# PowerDDFK.net
KiCad netlist of a schematic drawn in Altium Designer
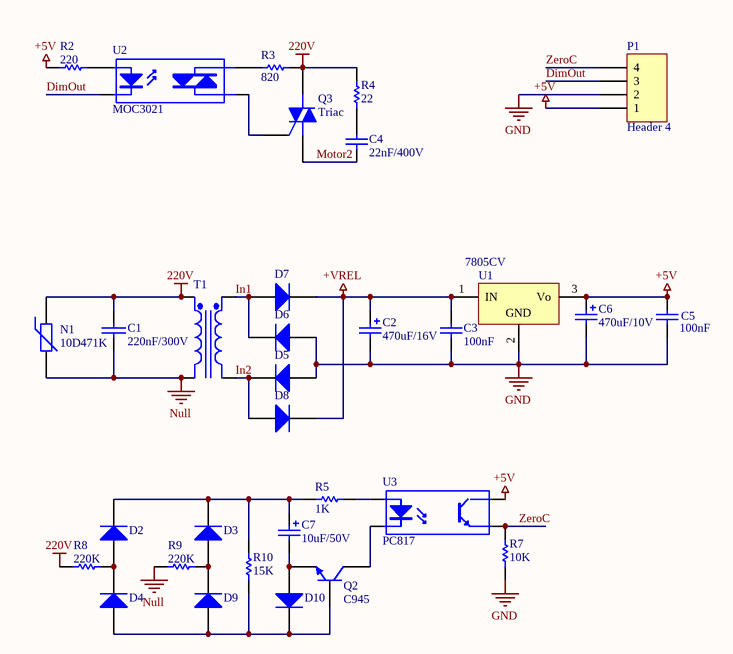
[diagram p0: PowerDDFK.SchDoc]

(export (version "E")
  (design (tool "Eeschema 10.0.6"))
  (components
    (comp (ref "C1")
      (value "220nF/300V")
      (footprint "Cap15-20")
      (description "Line Cap")
      (libsource (lib "*") (part "CAP"))
    )
    (comp (ref "C2")
      (value "470uF/16V")
      (footprint "RB.2/.4")
      (description "Polarized Capacitor")
      (fields (field (name "PUBLISHER") "Altium Limited"))
      (libsource (lib "MySchLib") (part "Cap Pol"))
    )
    (comp (ref "C3")
      (value "100nF")
      (footprint "RAD0.2")
      (description "Capacitor np")
      (fields (field (name "PUBLISHER") "Altium Limited"))
      (libsource (lib "MySchLib") (part "Cap"))
    )
    (comp (ref "C4")
      (value "22nF/400V")
      (footprint "Cap10")
      (description "Capacitor")
      (fields (field (name "PUBLISHER") "Altium Limited"))
      (libsource (lib "MySchLib") (part "Cap"))
    )
    (comp (ref "C5")
      (value "100nF")
      (footprint "RAD0.2")
      (description "Capacitor np")
      (fields (field (name "PUBLISHER") "Altium Limited"))
      (libsource (lib "MySchLib") (part "Cap"))
    )
    (comp (ref "C6")
      (value "470uF/10V")
      (footprint "RB.2/.4")
      (description "Polarized Capacitor")
      (fields (field (name "PUBLISHER") "Altium Limited"))
      (libsource (lib "MySchLib") (part "Cap Pol"))
    )
    (comp (ref "C7")
      (value "10uF/50V")
      (footprint "RB.1/.2")
      (description "Polarized Capacitor")
      (fields (field (name "PUBLISHER") "Altium Limited"))
      (libsource (lib "MySchLib") (part "Cap Pol"))
    )
    (comp (ref "D2")
      (value "1N4007")
      (footprint "DIODE0.4")
      (fields (field (name "PUBLISHER") "Altium Limited"))
      (libsource (lib "MySchLib") (part "Diode"))
    )
    (comp (ref "D3")
      (value "1N4007")
      (footprint "DIODE0.4")
      (fields (field (name "PUBLISHER") "Altium Limited"))
      (libsource (lib "MySchLib") (part "Diode"))
    )
    (comp (ref "D4")
      (value "1N4007")
      (footprint "DIODE0.4")
      (fields (field (name "PUBLISHER") "Altium Limited"))
      (libsource (lib "MySchLib") (part "Diode"))
    )
    (comp (ref "D5")
      (value "1N4007")
      (footprint "DIODE0.4")
      (fields (field (name "PUBLISHER") "Altium Limited"))
      (libsource (lib "MySchLib") (part "Diode"))
    )
    (comp (ref "D6")
      (value "1N4007")
      (footprint "DIODE0.4")
      (fields (field (name "PUBLISHER") "Altium Limited"))
      (libsource (lib "MySchLib") (part "Diode"))
    )
    (comp (ref "D7")
      (value "1N4007")
      (footprint "DIODE0.4")
      (fields (field (name "PUBLISHER") "Altium Limited"))
      (libsource (lib "MySchLib") (part "Diode"))
    )
    (comp (ref "D8")
      (value "1N4007")
      (footprint "DIODE0.4")
      (fields (field (name "PUBLISHER") "Altium Limited"))
      (libsource (lib "MySchLib") (part "Diode"))
    )
    (comp (ref "D9")
      (value "1N4007")
      (footprint "DIODE0.4")
      (fields (field (name "PUBLISHER") "Altium Limited"))
      (libsource (lib "MySchLib") (part "Diode"))
    )
    (comp (ref "D10")
      (value "1N4007")
      (footprint "DIODE0.4")
      (fields (field (name "PUBLISHER") "Altium Limited"))
      (libsource (lib "MySchLib") (part "Diode"))
    )
    (comp (ref "N1")
      (value "10D471K")
      (footprint "varistor-10mil")
      (fields (field (name "PUBLISHER") "Altium Limited"))
      (libsource (lib "Miscellaneous Devices") (part "Res Varistor"))
    )
    (comp (ref "P1")
      (value "Header 4")
      (footprint "CON4")
      (description "Header, 4-Pin")
      (fields (field (name "PUBLISHER") "Altium Limited"))
      (libsource (lib "Miscellaneous Connectors") (part "Header 4"))
    )
    (comp (ref "Q2")
      (value "C945")
      (footprint "TO92BS2")
      (description "NPN General Purpose Amplifier")
      (fields (field (name "PUBLISHER") "Altium Limited"))
      (libsource (lib "MySchLib") (part "BC337"))
    )
    (comp (ref "Q3")
      (value "Triac")
      (footprint "TO-220HS28")
      (description "Silicon Bidirectional Triode Thyristor")
      (fields (field (name "PUBLISHER") "Altium Limited"))
      (libsource (lib "Miscellaneous Devices") (part "Triac"))
    )
    (comp (ref "R2")
      (value "220")
      (footprint "RES0.35")
      (description "Resistor")
      (fields (field (name "PUBLISHER") "Altium Limited"))
      (libsource (lib "MySchLib") (part "Resistor"))
    )
    (comp (ref "R3")
      (value "820")
      (footprint "RES0.35")
      (description "Resistor")
      (fields (field (name "PUBLISHER") "Altium Limited"))
      (libsource (lib "MySchLib") (part "Resistor"))
    )
    (comp (ref "R4")
      (value "22")
      (footprint "RES0.35")
      (description "Resistor")
      (fields (field (name "PUBLISHER") "Altium Limited"))
      (libsource (lib "MySchLib") (part "Resistor"))
    )
    (comp (ref "R5")
      (value "1K")
      (footprint "RES0.35")
      (description "Resistor")
      (fields (field (name "PUBLISHER") "Altium Limited"))
      (libsource (lib "MySchLib") (part "Resistor"))
    )
    (comp (ref "R7")
      (value "10K")
      (footprint "RES0.35")
      (description "Resistor")
      (fields (field (name "PUBLISHER") "Altium Limited"))
      (libsource (lib "MySchLib") (part "Resistor"))
    )
    (comp (ref "R8")
      (value "220K")
      (footprint "RES0.35")
      (description "Resistor")
      (fields (field (name "PUBLISHER") "Altium Limited"))
      (libsource (lib "MySchLib") (part "Resistor"))
    )
    (comp (ref "R9")
      (value "220K")
      (footprint "RES0.35")
      (description "Resistor")
      (fields (field (name "PUBLISHER") "Altium Limited"))
      (libsource (lib "MySchLib") (part "Resistor"))
    )
    (comp (ref "R10")
      (value "15K")
      (footprint "RES0.35")
      (description "Resistor")
      (fields (field (name "PUBLISHER") "Altium Limited"))
      (libsource (lib "MySchLib") (part "Resistor"))
    )
    (comp (ref "T1")
      (value "Transformer")
      (footprint "Trans200mA")
      (description "6Volt-300mA")
      (fields (field (name "PUBLISHER") "Altium Limited"))
      (libsource (lib "MySchLib") (part "Transformer"))
    )
    (comp (ref "U1")
      (value "7805CV")
      (footprint "TO-220HS28")
      (description "Positive Voltage Regulator")
      (fields (field (name "PUBLISHER") "Altium Limited"))
      (libsource (lib "MySchLib") (part "7805"))
    )
    (comp (ref "U2")
      (value "MOC3021")
      (footprint "DIP6")
      (description "Opto-Triac")
      (fields (field (name "PUBLISHER") "Altium Limited"))
      (libsource (lib "MySchLib") (part "Opto TRIAC_1"))
    )
    (comp (ref "U3")
      (value "PC817")
      (footprint "DIP4-OPTO")
      (description "4-Pin Phototransistor Optocoupler")
      (fields (field (name "PUBLISHER") "Altium Limited"))
      (libsource (lib "MySchLib") (part "Optoisolator1"))
    )
  )
  (nets
    (net (code "1") (name "+5V") (class "Default")
      (node (ref "C5") (pin "2") (pinfunction "2_2") (pintype "passive"))
      (node (ref "C6") (pin "1") (pinfunction "1_1") (pintype "passive"))
      (node (ref "P1") (pin "1") (pinfunction "1_1") (pintype "passive"))
      (node (ref "R2") (pin "1") (pinfunction "1_1") (pintype "passive"))
      (node (ref "U1") (pin "3") (pinfunction "Vo_3") (pintype "power_in"))
      (node (ref "U3") (pin "4") (pinfunction "C_4") (pintype "passive"))
    )
    (net (code "2") (name "+VREL") (class "Default")
      (node (ref "C2") (pin "1") (pinfunction "1_1") (pintype "passive"))
      (node (ref "C3") (pin "2") (pinfunction "2_2") (pintype "passive"))
      (node (ref "D7") (pin "2") (pinfunction "K_2") (pintype "passive"))
      (node (ref "D8") (pin "2") (pinfunction "K_2") (pintype "passive"))
      (node (ref "U1") (pin "1") (pinfunction "IN_1") (pintype "power_in"))
    )
    (net (code "3") (name "/DimOut") (class "Default")
      (node (ref "P1") (pin "3") (pinfunction "3_3") (pintype "passive"))
      (node (ref "U2") (pin "2") (pinfunction "K_2") (pintype "passive"))
    )
    (net (code "4") (name "/In1") (class "Default")
      (node (ref "D6") (pin "2") (pinfunction "K_2") (pintype "passive"))
      (node (ref "D7") (pin "1") (pinfunction "A_1") (pintype "passive"))
      (node (ref "T1") (pin "3") (pinfunction "Sec+_3") (pintype "passive"))
    )
    (net (code "5") (name "/In2") (class "Default")
      (node (ref "D5") (pin "2") (pinfunction "K_2") (pintype "passive"))
      (node (ref "D8") (pin "1") (pinfunction "A_1") (pintype "passive"))
      (node (ref "T1") (pin "4") (pinfunction "Sec-_4") (pintype "passive"))
    )
    (net (code "6") (name "/Motor2") (class "Default")
      (node (ref "C4") (pin "1") (pinfunction "1_1") (pintype "passive"))
      (node (ref "Q3") (pin "1") (pinfunction "M1_1") (pintype "passive"))
    )
    (net (code "7") (name "/ZeroC") (class "Default")
      (node (ref "P1") (pin "4") (pinfunction "4_4") (pintype "passive"))
      (node (ref "R7") (pin "1") (pinfunction "1_1") (pintype "passive"))
      (node (ref "U3") (pin "3") (pinfunction "E_3") (pintype "passive"))
    )
    (net (code "8") (name "220V") (class "Default")
      (node (ref "C1") (pin "1") (pinfunction "1_1") (pintype "passive"))
      (node (ref "N1") (pin "1") (pinfunction "1_1") (pintype "passive"))
      (node (ref "Q3") (pin "2") (pinfunction "M2_2") (pintype "passive"))
      (node (ref "R3") (pin "1") (pinfunction "1_1") (pintype "passive"))
      (node (ref "R4") (pin "1") (pinfunction "1_1") (pintype "passive"))
      (node (ref "R8") (pin "1") (pinfunction "1_1") (pintype "passive"))
      (node (ref "T1") (pin "1") (pinfunction "Pri+_1") (pintype "passive"))
    )
    (net (code "9") (name "GND") (class "Default")
      (node (ref "C2") (pin "2") (pinfunction "2_2") (pintype "passive"))
      (node (ref "C3") (pin "1") (pinfunction "1_1") (pintype "passive"))
      (node (ref "C5") (pin "1") (pinfunction "1_1") (pintype "passive"))
      (node (ref "C6") (pin "2") (pinfunction "2_2") (pintype "passive"))
      (node (ref "D5") (pin "1") (pinfunction "A_1") (pintype "passive"))
      (node (ref "D6") (pin "1") (pinfunction "A_1") (pintype "passive"))
      (node (ref "P1") (pin "2") (pinfunction "2_2") (pintype "passive"))
      (node (ref "R7") (pin "2") (pinfunction "2_2") (pintype "passive"))
      (node (ref "U1") (pin "2") (pinfunction "OUT_2") (pintype "power_in"))
    )
    (net (code "10") (name "Net-(C4-Pad2)") (class "Default")
      (node (ref "C4") (pin "2") (pinfunction "2_2") (pintype "passive"))
      (node (ref "R4") (pin "2") (pinfunction "2_2") (pintype "passive"))
    )
    (net (code "11") (name "Net-(D2-A)") (class "Default")
      (node (ref "D2") (pin "1") (pinfunction "A_1") (pintype "passive"))
      (node (ref "D4") (pin "2") (pinfunction "K_2") (pintype "passive"))
      (node (ref "R8") (pin "2") (pinfunction "2_2") (pintype "passive"))
    )
    (net (code "12") (name "Net-(D2-K)") (class "Default")
      (node (ref "C7") (pin "1") (pinfunction "1_1") (pintype "passive"))
      (node (ref "D2") (pin "2") (pinfunction "K_2") (pintype "passive"))
      (node (ref "D3") (pin "2") (pinfunction "K_2") (pintype "passive"))
      (node (ref "R10") (pin "2") (pinfunction "2_2") (pintype "passive"))
      (node (ref "R5") (pin "2") (pinfunction "2_2") (pintype "passive"))
    )
    (net (code "13") (name "Net-(D3-A)") (class "Default")
      (node (ref "D3") (pin "1") (pinfunction "A_1") (pintype "passive"))
      (node (ref "D9") (pin "2") (pinfunction "K_2") (pintype "passive"))
      (node (ref "R9") (pin "2") (pinfunction "2_2") (pintype "passive"))
    )
    (net (code "14") (name "Net-(D10-A)") (class "Default")
      (node (ref "C7") (pin "2") (pinfunction "2_2") (pintype "passive"))
      (node (ref "D10") (pin "1") (pinfunction "A_1") (pintype "passive"))
      (node (ref "Q2") (pin "3") (pinfunction "E_3") (pintype "passive"))
    )
    (net (code "15") (name "Net-(D10-K)") (class "Default")
      (node (ref "D10") (pin "2") (pinfunction "K_2") (pintype "passive"))
      (node (ref "D4") (pin "1") (pinfunction "A_1") (pintype "passive"))
      (node (ref "D9") (pin "1") (pinfunction "A_1") (pintype "passive"))
      (node (ref "Q2") (pin "1") (pinfunction "B_1") (pintype "passive"))
      (node (ref "R10") (pin "1") (pinfunction "1_1") (pintype "passive"))
    )
    (net (code "16") (name "Net-(Q2-C)") (class "Default")
      (node (ref "Q2") (pin "2") (pinfunction "C_2") (pintype "passive"))
      (node (ref "U3") (pin "2") (pinfunction "K_2") (pintype "passive"))
    )
    (net (code "17") (name "Net-(Q3-G)") (class "Default")
      (node (ref "Q3") (pin "3") (pinfunction "G_3") (pintype "passive"))
      (node (ref "U2") (pin "4") (pinfunction "A/K_4") (pintype "passive"))
    )
    (net (code "18") (name "Net-(R3-Pad2)") (class "Default")
      (node (ref "R3") (pin "2") (pinfunction "2_2") (pintype "passive"))
      (node (ref "U2") (pin "6") (pinfunction "A/K_6") (pintype "passive"))
    )
    (net (code "19") (name "Net-(U2-A)") (class "Default")
      (node (ref "R2") (pin "2") (pinfunction "2_2") (pintype "passive"))
      (node (ref "U2") (pin "1") (pinfunction "A_1") (pintype "passive"))
    )
    (net (code "20") (name "Net-(U3-A)") (class "Default")
      (node (ref "R5") (pin "1") (pinfunction "1_1") (pintype "passive"))
      (node (ref "U3") (pin "1") (pinfunction "A_1") (pintype "passive"))
    )
    (net (code "21") (name "Null") (class "Default")
      (node (ref "C1") (pin "2") (pinfunction "2_2") (pintype "passive"))
      (node (ref "N1") (pin "2") (pinfunction "2_2") (pintype "passive"))
      (node (ref "R9") (pin "1") (pinfunction "1_1") (pintype "passive"))
      (node (ref "T1") (pin "2") (pinfunction "Pri-_2") (pintype "passive"))
    )
  )
)
